# miniArcadeEasyEDA.net
KiCad netlist of a schematic drawn in EasyEDA
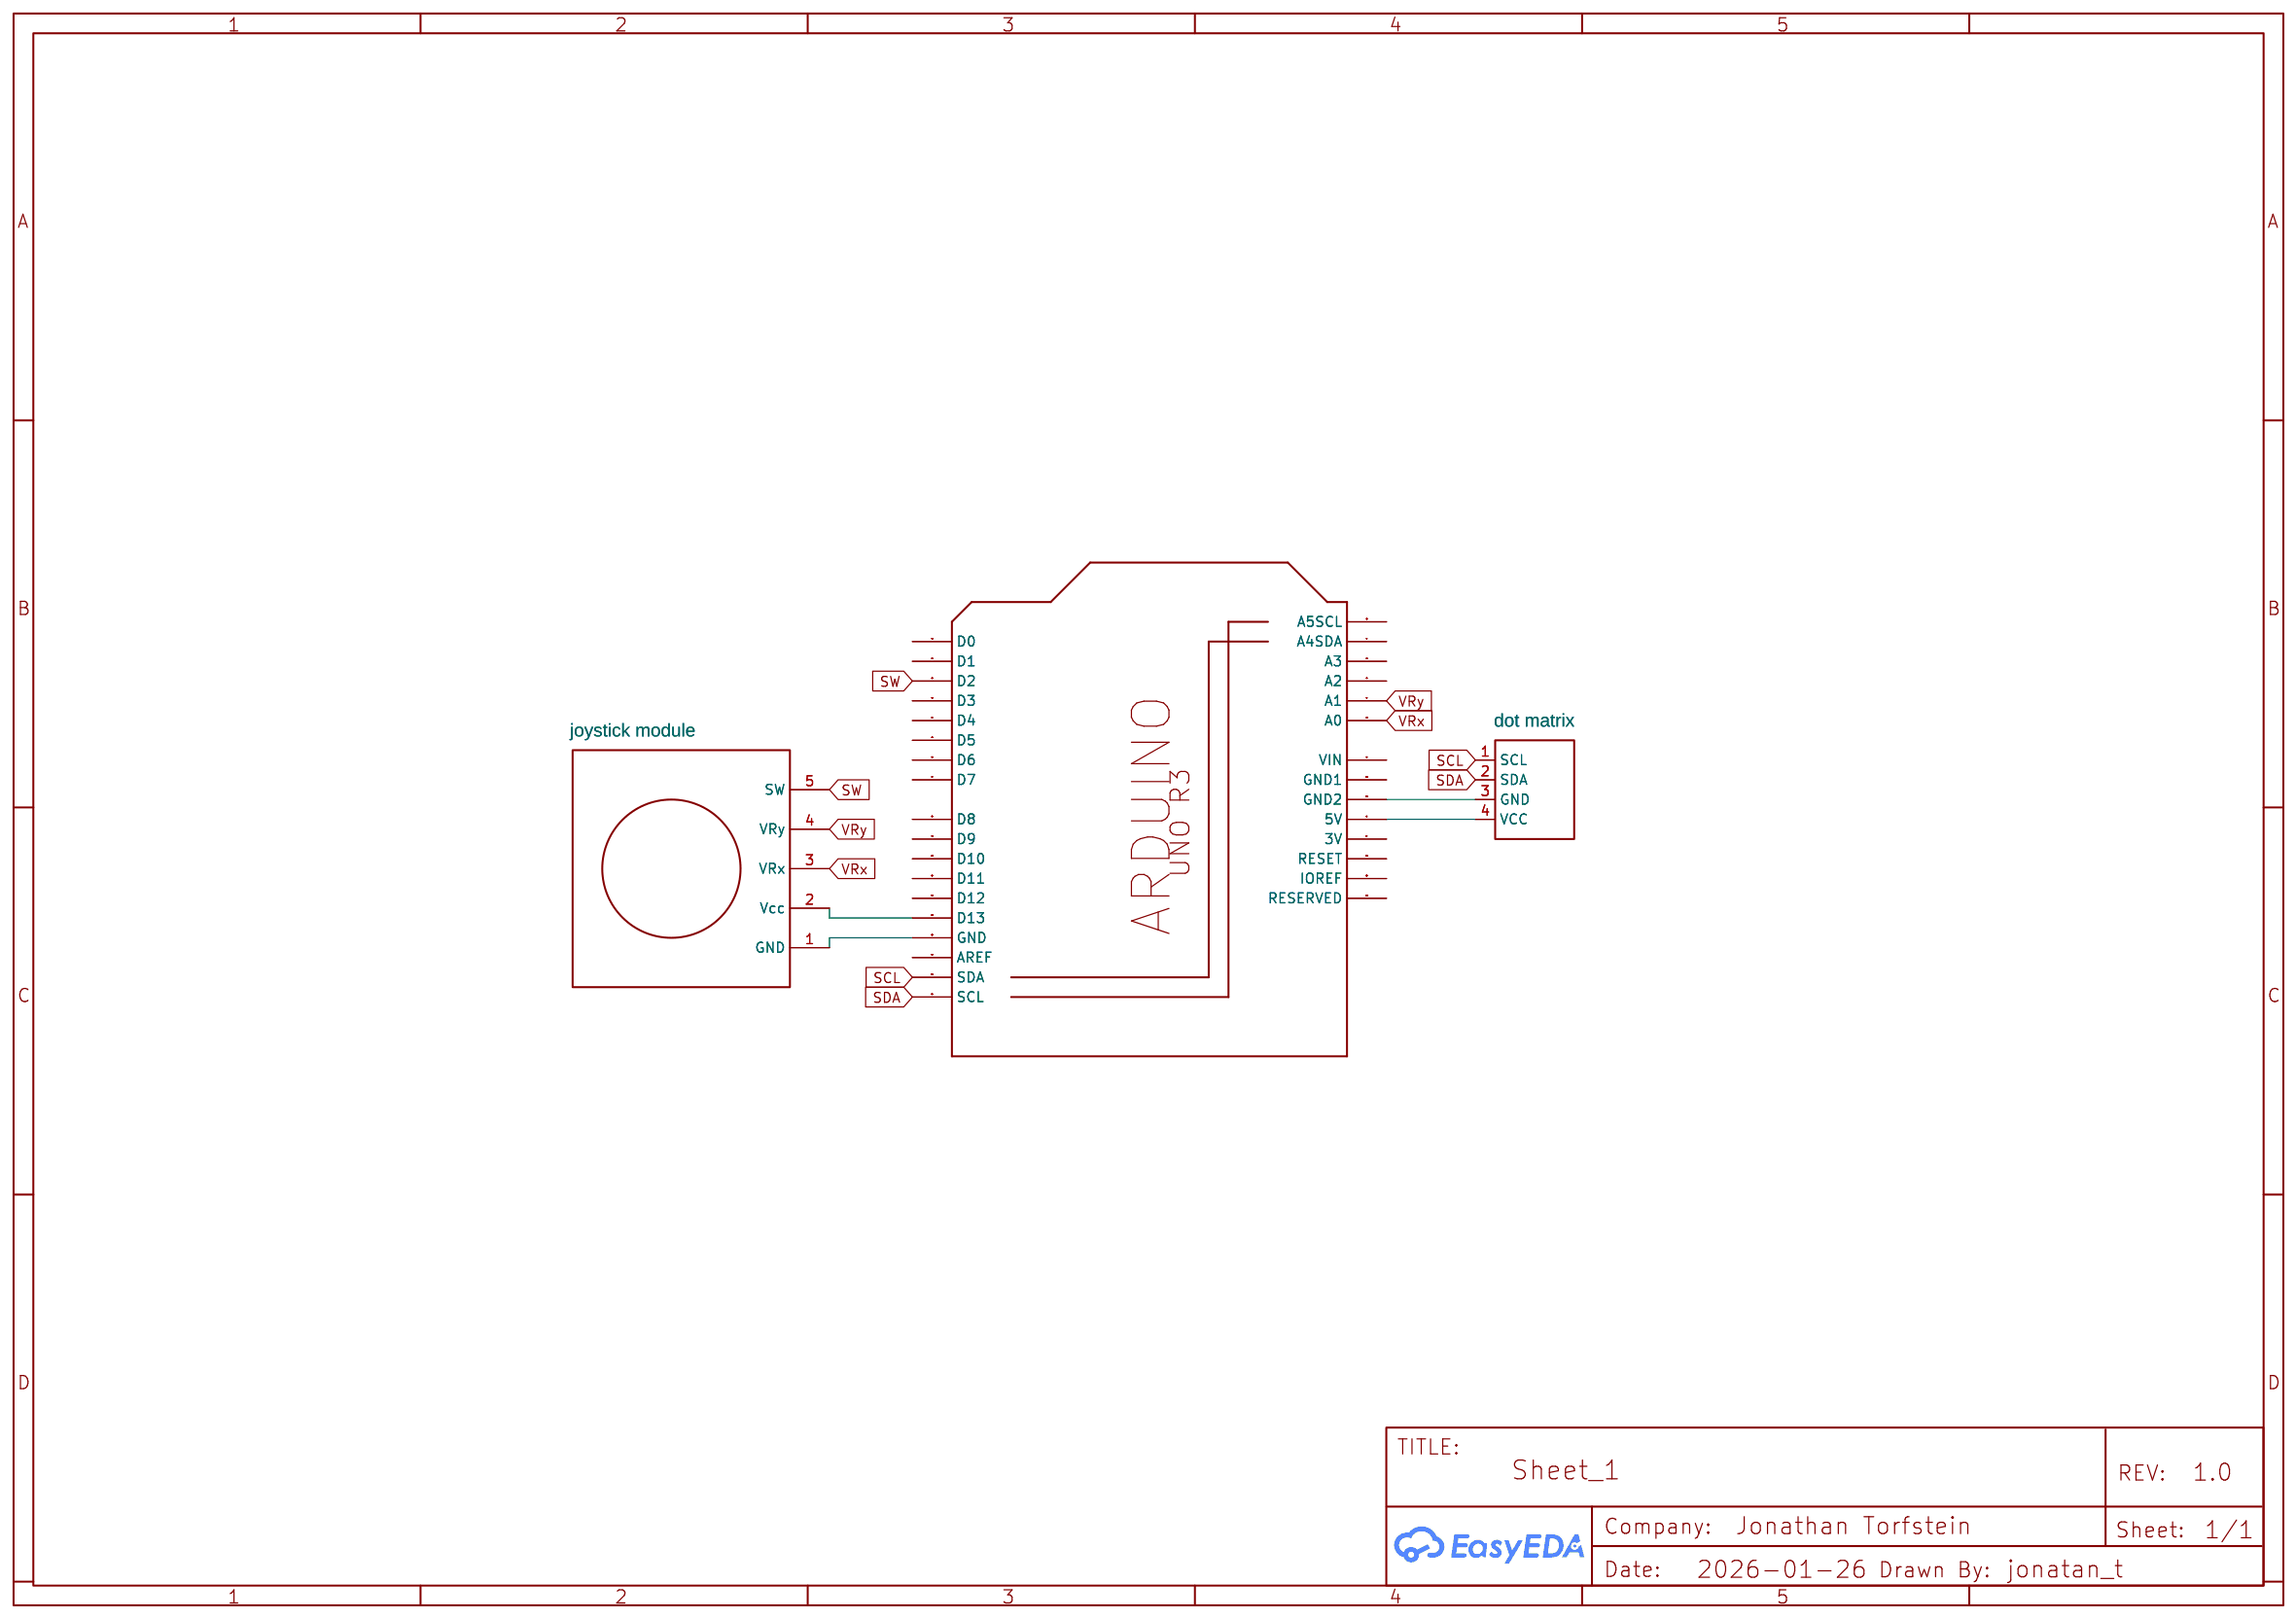
[diagram p0: schematic sheet]

(export (version "E")
  (design (tool "Eeschema 10.0.6"))
  (components
    (comp (ref "U1") (value "ARDUINOR3-DIMENSION") (libsource (lib "") (part "ARDUINOR3-DIMENSION")))
    (comp (ref "U2")
      (value "dot matrix")
      (fields
        (field (name "Manufacturer Part") "350424-1")
        (field (name "Manufacturer") "TE Connectivity(泰科电子)")
      )
      (libsource (lib "") (part "350424-1"))
    )
    (comp (ref "U3") (value "joystick module") (libsource (lib "") (part "HW-504JOYSTICK")))
  )
  (nets
    (net (code "1") (name "Net-(U2-GND)") (class "Default")
      (node (ref "U1") (pin "GND2") (pinfunction "GND2_GND2") (pintype "passive"))
      (node (ref "U2") (pin "3") (pinfunction "GND_3") (pintype "unspecified"))
    )
    (net (code "2") (name "Net-(U2-VCC)") (class "Default")
      (node (ref "U1") (pin "5V") (pinfunction "5V_5V") (pintype "passive"))
      (node (ref "U2") (pin "4") (pinfunction "VCC_4") (pintype "unspecified"))
    )
    (net (code "3") (name "Net-(U3-GND)") (class "Default")
      (node (ref "U1") (pin "GND") (pinfunction "GND_GND") (pintype "passive"))
      (node (ref "U3") (pin "1") (pinfunction "GND_1") (pintype "unspecified"))
    )
    (net (code "4") (name "Net-(U3-Vcc)") (class "Default")
      (node (ref "U1") (pin "D13") (pinfunction "D13_D13") (pintype "unspecified"))
      (node (ref "U3") (pin "2") (pinfunction "Vcc_2") (pintype "unspecified"))
    )
    (net (code "5") (name "SCL") (class "Default")
      (node (ref "U1") (pin "SDA") (pinfunction "SDA_SDA") (pintype "unspecified"))
      (node (ref "U2") (pin "1") (pinfunction "SCL_1") (pintype "unspecified"))
    )
    (net (code "6") (name "SDA") (class "Default")
      (node (ref "U1") (pin "SCL") (pinfunction "SCL_SCL") (pintype "unspecified"))
      (node (ref "U2") (pin "2") (pinfunction "SDA_2") (pintype "unspecified"))
    )
    (net (code "7") (name "SW") (class "Default")
      (node (ref "U1") (pin "D2") (pinfunction "D2_D2") (pintype "unspecified"))
      (node (ref "U3") (pin "5") (pinfunction "SW_5") (pintype "unspecified"))
    )
    (net (code "8") (name "VRx") (class "Default")
      (node (ref "U1") (pin "A0") (pinfunction "A0_A0") (pintype "unspecified"))
      (node (ref "U3") (pin "3") (pinfunction "VRx_3") (pintype "unspecified"))
    )
    (net (code "9") (name "VRy") (class "Default")
      (node (ref "U1") (pin "A1") (pinfunction "A1_A1") (pintype "unspecified"))
      (node (ref "U3") (pin "4") (pinfunction "VRy_4") (pintype "unspecified"))
    )
    (net (code "10") (name "unconnected-(U1-A4SDA-PadA4)") (class "Default")
      (node (ref "U1") (pin "A4") (pinfunction "A4SDA_A4") (pintype "unspecified"))
    )
    (net (code "11") (name "unconnected-(U1-A5SCL-PadA5)") (class "Default")
      (node (ref "U1") (pin "A5") (pinfunction "A5SCL_A5") (pintype "unspecified"))
    )
    (net (code "12") (name "unconnected-(U1-Pad3V)") (class "Default")
      (node (ref "U1") (pin "3V") (pinfunction "3V_3V") (pintype "passive"))
    )
    (net (code "13") (name "unconnected-(U1-PadA2)") (class "Default")
      (node (ref "U1") (pin "A2") (pinfunction "A2_A2") (pintype "unspecified"))
    )
    (net (code "14") (name "unconnected-(U1-PadA3)") (class "Default")
      (node (ref "U1") (pin "A3") (pinfunction "A3_A3") (pintype "unspecified"))
    )
    (net (code "15") (name "unconnected-(U1-PadAREF)") (class "Default")
      (node (ref "U1") (pin "AREF") (pinfunction "AREF_AREF") (pintype "unspecified"))
    )
    (net (code "16") (name "unconnected-(U1-PadD0)") (class "Default")
      (node (ref "U1") (pin "D0") (pinfunction "D0_D0") (pintype "unspecified"))
    )
    (net (code "17") (name "unconnected-(U1-PadD1)") (class "Default")
      (node (ref "U1") (pin "D1") (pinfunction "D1_D1") (pintype "unspecified"))
    )
    (net (code "18") (name "unconnected-(U1-PadD3)") (class "Default")
      (node (ref "U1") (pin "D3") (pinfunction "D3_D3") (pintype "unspecified"))
    )
    (net (code "19") (name "unconnected-(U1-PadD4)") (class "Default")
      (node (ref "U1") (pin "D4") (pinfunction "D4_D4") (pintype "unspecified"))
    )
    (net (code "20") (name "unconnected-(U1-PadD5)") (class "Default")
      (node (ref "U1") (pin "D5") (pinfunction "D5_D5") (pintype "unspecified"))
    )
    (net (code "21") (name "unconnected-(U1-PadD6)") (class "Default")
      (node (ref "U1") (pin "D6") (pinfunction "D6_D6") (pintype "unspecified"))
    )
    (net (code "22") (name "unconnected-(U1-PadD7)") (class "Default")
      (node (ref "U1") (pin "D7") (pinfunction "D7_D7") (pintype "unspecified"))
    )
    (net (code "23") (name "unconnected-(U1-PadD8)") (class "Default")
      (node (ref "U1") (pin "D8") (pinfunction "D8_D8") (pintype "unspecified"))
    )
    (net (code "24") (name "unconnected-(U1-PadD9)") (class "Default")
      (node (ref "U1") (pin "D9") (pinfunction "D9_D9") (pintype "unspecified"))
    )
    (net (code "25") (name "unconnected-(U1-PadD10)") (class "Default")
      (node (ref "U1") (pin "D10") (pinfunction "D10_D10") (pintype "unspecified"))
    )
    (net (code "26") (name "unconnected-(U1-PadD11)") (class "Default")
      (node (ref "U1") (pin "D11") (pinfunction "D11_D11") (pintype "unspecified"))
    )
    (net (code "27") (name "unconnected-(U1-PadD12)") (class "Default")
      (node (ref "U1") (pin "D12") (pinfunction "D12_D12") (pintype "unspecified"))
    )
    (net (code "28") (name "unconnected-(U1-PadGND1)") (class "Default")
      (node (ref "U1") (pin "GND1") (pinfunction "GND1_GND1") (pintype "passive"))
    )
    (net (code "29") (name "unconnected-(U1-PadIOREF)") (class "Default")
      (node (ref "U1") (pin "IOREF") (pinfunction "IOREF_IOREF") (pintype "output"))
    )
    (net (code "30") (name "unconnected-(U1-PadRESERVED)") (class "Default")
      (node (ref "U1") (pin "RESERVED") (pinfunction "RESERVED_RESERVED") (pintype "unspecified"))
    )
    (net (code "31") (name "unconnected-(U1-PadRESET)") (class "Default")
      (node (ref "U1") (pin "RESET") (pinfunction "RESET_RESET") (pintype "unspecified"))
    )
    (net (code "32") (name "unconnected-(U1-PadVIN)") (class "Default")
      (node (ref "U1") (pin "VIN") (pinfunction "VIN_VIN") (pintype "passive"))
    )
  )
)
